# m14sim.net
KiCad netlist of a schematic drawn in Altium Designer
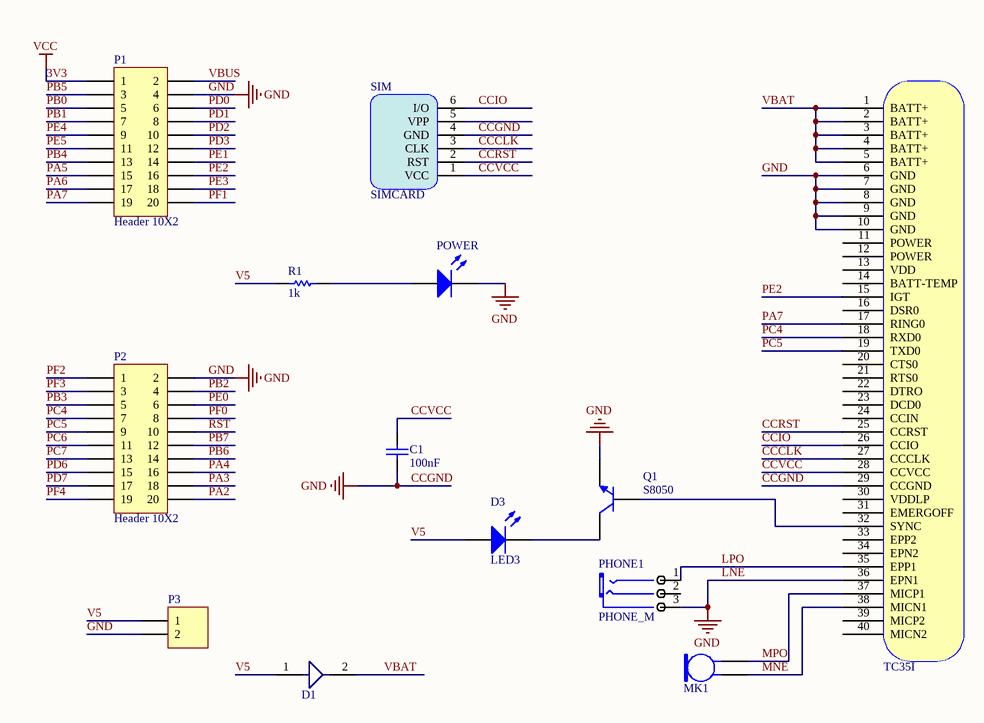
[diagram p0: m14sim.SchDoc]

(export (version "E")
  (design (tool "Eeschema 10.0.6"))
  (components
    (comp (ref "C1")
      (value "100nF")
      (footprint "CAP_0805")
      (description "Capacitor (Semiconductor SIM Model)")
      (fields (field (name "Comment") "Cap Semi") (field (name "PUBLISHER") "Altium Limited"))
      (libsource (lib "Miscellaneous Devices") (part "Cap Semi"))
    )
    (comp (ref "D1") (value "DIAO") (footprint "DIAO") (libsource (lib "LMP3") (part "DIAO")))
    (comp (ref "D3")
      (value "LED3")
      (footprint "LED_0603_RED")
      (description "Typical RED GaAs LED")
      (fields (field (name "PUBLISHER") "Altium Limited"))
      (libsource (lib "Miscellaneous Devices") (part "LED1"))
    )
    (comp (ref "MK1")
      (value "Mic2")
      (footprint "PIN2")
      (description "Microphone")
      (fields (field (name "PUBLISHER") "Altium Limited"))
      (libsource (lib "Miscellaneous Devices") (part "Mic2"))
    )
    (comp (ref "P1")
      (value "Header 10X2")
      (footprint "HDR2X10")
      (description "Header, 10-Pin, Dual row")
      (fields (field (name "PUBLISHER") "Altium Limited"))
      (libsource (lib "Miscellaneous Connectors") (part "Header 10X2"))
    )
    (comp (ref "P2")
      (value "Header 10X2")
      (footprint "HDR2X10")
      (description "Header, 10-Pin, Dual row")
      (fields (field (name "PUBLISHER") "Altium Limited"))
      (libsource (lib "Miscellaneous Connectors") (part "Header 10X2"))
    )
    (comp (ref "P3")
      (value "Header 2")
      (footprint "MKDSN_2RMI")
      (description "Header, 2-Pin")
      (fields (field (name "PUBLISHER") "Altium Limited"))
      (libsource (lib "Miscellaneous Connectors") (part "Header 2"))
    )
    (comp (ref "PHONE1")
      (value "PHONE_M")
      (footprint "PHONE_ST")
      (libsource (lib "战舰STM32开发板底板封装库") (part "PHONE_M"))
    )
    (comp (ref "POWER")
      (value "POWER")
      (footprint "LED_0603_RED")
      (description "Typical RED GaAs LED")
      (fields (field (name "PUBLISHER") "Altium Limited"))
      (libsource (lib "Miscellaneous Devices") (part "LED1"))
    )
    (comp (ref "Q1")
      (value "S8050")
      (footprint "SOT23")
      (description "NPN General-purpose Transistor")
      (fields (field (name "PUBLISHER") "Altium Limited"))
      (libsource (lib "Philips Discrete BJT - Low Power") (part "BC848W"))
    )
    (comp (ref "R1")
      (value "1k")
      (footprint "RES_0603")
      (description "Semiconductor Resistor")
      (fields (field (name "Comment") "Res Semi") (field (name "PUBLISHER") "Altium Limited"))
      (libsource (lib "Miscellaneous Devices") (part "Res Semi"))
    )
    (comp (ref "SIM") (value "SIMCARD") (footprint "SIM6") (libsource (lib "GSM") (part "SIMCARD")))
    (comp (ref "ZIF40") (value "TC35I") (footprint "ZIF") (libsource (lib "GSM") (part "TC35I")))
  )
  (nets
    (net (code "1") (name "/CCCLK") (class "Default")
      (node (ref "SIM") (pin "3") (pinfunction "CLK_3") (pintype "passive"))
      (node (ref "ZIF40") (pin "27") (pinfunction "CCCLK_27") (pintype "passive"))
    )
    (net (code "2") (name "/CCIO") (class "Default")
      (node (ref "SIM") (pin "6") (pinfunction "I/O_6") (pintype "passive"))
      (node (ref "ZIF40") (pin "26") (pinfunction "CCIO_26") (pintype "passive"))
    )
    (net (code "3") (name "/CCRST") (class "Default")
      (node (ref "SIM") (pin "2") (pinfunction "RST_2") (pintype "passive"))
      (node (ref "ZIF40") (pin "25") (pinfunction "CCRST_25") (pintype "passive"))
    )
    (net (code "4") (name "/CCVCC") (class "Default")
      (node (ref "C1") (pin "2") (pinfunction "2_2") (pintype "passive"))
      (node (ref "SIM") (pin "1") (pinfunction "VCC_1") (pintype "passive"))
      (node (ref "ZIF40") (pin "28") (pinfunction "CCVCC_28") (pintype "passive"))
    )
    (net (code "5") (name "/LPO") (class "Default")
      (node (ref "PHONE1") (pin "1") (pinfunction "CHL_1") (pintype "passive"))
      (node (ref "ZIF40") (pin "35") (pinfunction "EPP1_35") (pintype "passive"))
    )
    (net (code "6") (name "/MNE") (class "Default")
      (node (ref "MK1") (pin "1") (pinfunction "1_1") (pintype "passive"))
      (node (ref "ZIF40") (pin "38") (pinfunction "MICN1_38") (pintype "passive"))
    )
    (net (code "7") (name "/MPO") (class "Default")
      (node (ref "MK1") (pin "2") (pinfunction "2_2") (pintype "passive"))
      (node (ref "ZIF40") (pin "37") (pinfunction "MICP1_37") (pintype "passive"))
    )
    (net (code "8") (name "/PA2") (class "Default")
      (node (ref "P2") (pin "20") (pinfunction "20_20") (pintype "passive"))
    )
    (net (code "9") (name "/PA3") (class "Default")
      (node (ref "P2") (pin "18") (pinfunction "18_18") (pintype "passive"))
    )
    (net (code "10") (name "/PA4") (class "Default")
      (node (ref "P2") (pin "16") (pinfunction "16_16") (pintype "passive"))
    )
    (net (code "11") (name "/PA5") (class "Default")
      (node (ref "P1") (pin "15") (pinfunction "15_15") (pintype "passive"))
    )
    (net (code "12") (name "/PA6") (class "Default")
      (node (ref "P1") (pin "17") (pinfunction "17_17") (pintype "passive"))
    )
    (net (code "13") (name "/PA7") (class "Default")
      (node (ref "P1") (pin "19") (pinfunction "19_19") (pintype "passive"))
      (node (ref "ZIF40") (pin "17") (pinfunction "RING0_17") (pintype "passive"))
    )
    (net (code "14") (name "/PB0") (class "Default")
      (node (ref "P1") (pin "5") (pinfunction "5_5") (pintype "passive"))
    )
    (net (code "15") (name "/PB1") (class "Default")
      (node (ref "P1") (pin "7") (pinfunction "7_7") (pintype "passive"))
    )
    (net (code "16") (name "/PB2") (class "Default")
      (node (ref "P2") (pin "4") (pinfunction "4_4") (pintype "passive"))
    )
    (net (code "17") (name "/PB3") (class "Default")
      (node (ref "P2") (pin "5") (pinfunction "5_5") (pintype "passive"))
    )
    (net (code "18") (name "/PB4") (class "Default")
      (node (ref "P1") (pin "13") (pinfunction "13_13") (pintype "passive"))
    )
    (net (code "19") (name "/PB5") (class "Default")
      (node (ref "P1") (pin "3") (pinfunction "3_3") (pintype "passive"))
    )
    (net (code "20") (name "/PB6") (class "Default")
      (node (ref "P2") (pin "14") (pinfunction "14_14") (pintype "passive"))
    )
    (net (code "21") (name "/PB7") (class "Default")
      (node (ref "P2") (pin "12") (pinfunction "12_12") (pintype "passive"))
    )
    (net (code "22") (name "/PC4") (class "Default")
      (node (ref "P2") (pin "7") (pinfunction "7_7") (pintype "passive"))
      (node (ref "ZIF40") (pin "18") (pinfunction "RXD0_18") (pintype "passive"))
    )
    (net (code "23") (name "/PC5") (class "Default")
      (node (ref "P2") (pin "9") (pinfunction "9_9") (pintype "passive"))
      (node (ref "ZIF40") (pin "19") (pinfunction "TXD0_19") (pintype "passive"))
    )
    (net (code "24") (name "/PC6") (class "Default")
      (node (ref "P2") (pin "11") (pinfunction "11_11") (pintype "passive"))
    )
    (net (code "25") (name "/PC7") (class "Default")
      (node (ref "P2") (pin "13") (pinfunction "13_13") (pintype "passive"))
    )
    (net (code "26") (name "/PD0") (class "Default")
      (node (ref "P1") (pin "6") (pinfunction "6_6") (pintype "passive"))
    )
    (net (code "27") (name "/PD1") (class "Default")
      (node (ref "P1") (pin "8") (pinfunction "8_8") (pintype "passive"))
    )
    (net (code "28") (name "/PD2") (class "Default")
      (node (ref "P1") (pin "10") (pinfunction "10_10") (pintype "passive"))
    )
    (net (code "29") (name "/PD3") (class "Default")
      (node (ref "P1") (pin "12") (pinfunction "12_12") (pintype "passive"))
    )
    (net (code "30") (name "/PD6") (class "Default")
      (node (ref "P2") (pin "15") (pinfunction "15_15") (pintype "passive"))
    )
    (net (code "31") (name "/PD7") (class "Default")
      (node (ref "P2") (pin "17") (pinfunction "17_17") (pintype "passive"))
    )
    (net (code "32") (name "/PE0") (class "Default")
      (node (ref "P2") (pin "6") (pinfunction "6_6") (pintype "passive"))
    )
    (net (code "33") (name "/PE1") (class "Default")
      (node (ref "P1") (pin "14") (pinfunction "14_14") (pintype "passive"))
    )
    (net (code "34") (name "/PE2") (class "Default")
      (node (ref "P1") (pin "16") (pinfunction "16_16") (pintype "passive"))
      (node (ref "ZIF40") (pin "15") (pinfunction "IGT_15") (pintype "passive"))
    )
    (net (code "35") (name "/PE3") (class "Default")
      (node (ref "P1") (pin "18") (pinfunction "18_18") (pintype "passive"))
    )
    (net (code "36") (name "/PE4") (class "Default")
      (node (ref "P1") (pin "9") (pinfunction "9_9") (pintype "passive"))
    )
    (net (code "37") (name "/PE5") (class "Default")
      (node (ref "P1") (pin "11") (pinfunction "11_11") (pintype "passive"))
    )
    (net (code "38") (name "/PF0") (class "Default")
      (node (ref "P2") (pin "8") (pinfunction "8_8") (pintype "passive"))
    )
    (net (code "39") (name "/PF1") (class "Default")
      (node (ref "P1") (pin "20") (pinfunction "20_20") (pintype "passive"))
    )
    (net (code "40") (name "/PF2") (class "Default")
      (node (ref "P2") (pin "1") (pinfunction "1_1") (pintype "passive"))
    )
    (net (code "41") (name "/PF3") (class "Default")
      (node (ref "P2") (pin "3") (pinfunction "3_3") (pintype "passive"))
    )
    (net (code "42") (name "/PF4") (class "Default")
      (node (ref "P2") (pin "19") (pinfunction "19_19") (pintype "passive"))
    )
    (net (code "43") (name "/RST") (class "Default")
      (node (ref "P2") (pin "10") (pinfunction "10_10") (pintype "passive"))
    )
    (net (code "44") (name "/V5") (class "Default")
      (node (ref "D1") (pin "1") (pinfunction "1_1") (pintype "passive"))
      (node (ref "D3") (pin "1") (pinfunction "A_1") (pintype "passive"))
      (node (ref "P3") (pin "1") (pinfunction "1_1") (pintype "passive"))
      (node (ref "R1") (pin "2") (pinfunction "2_2") (pintype "passive"))
    )
    (net (code "45") (name "/VBAT") (class "Default")
      (node (ref "D1") (pin "2") (pinfunction "2_2") (pintype "passive"))
      (node (ref "ZIF40") (pin "1") (pinfunction "BATT+_1") (pintype "passive"))
      (node (ref "ZIF40") (pin "2") (pinfunction "BATT+_2") (pintype "passive"))
      (node (ref "ZIF40") (pin "3") (pinfunction "BATT+_3") (pintype "passive"))
      (node (ref "ZIF40") (pin "4") (pinfunction "BATT+_4") (pintype "passive"))
      (node (ref "ZIF40") (pin "5") (pinfunction "BATT+_5") (pintype "passive"))
    )
    (net (code "46") (name "/VBUS") (class "Default")
      (node (ref "P1") (pin "2") (pinfunction "2_2") (pintype "passive"))
    )
    (net (code "47") (name "GND") (class "Default")
      (node (ref "C1") (pin "1") (pinfunction "1_1") (pintype "passive"))
      (node (ref "P1") (pin "4") (pinfunction "4_4") (pintype "passive"))
      (node (ref "P2") (pin "2") (pinfunction "2_2") (pintype "passive"))
      (node (ref "P3") (pin "2") (pinfunction "2_2") (pintype "passive"))
      (node (ref "PHONE1") (pin "3") (pinfunction "COM_3") (pintype "passive"))
      (node (ref "POWER") (pin "2") (pinfunction "K_2") (pintype "passive"))
      (node (ref "Q1") (pin "2") (pinfunction "E_2") (pintype "passive"))
      (node (ref "SIM") (pin "4") (pinfunction "GND_4") (pintype "passive"))
      (node (ref "ZIF40") (pin "10") (pinfunction "GND_10") (pintype "passive"))
      (node (ref "ZIF40") (pin "29") (pinfunction "CCGND_29") (pintype "passive"))
      (node (ref "ZIF40") (pin "36") (pinfunction "EPN1_36") (pintype "passive"))
      (node (ref "ZIF40") (pin "6") (pinfunction "GND_6") (pintype "passive"))
      (node (ref "ZIF40") (pin "7") (pinfunction "GND_7") (pintype "passive"))
      (node (ref "ZIF40") (pin "8") (pinfunction "GND_8") (pintype "passive"))
      (node (ref "ZIF40") (pin "9") (pinfunction "GND_9") (pintype "passive"))
    )
    (net (code "48") (name "Net-(D3-K)") (class "Default")
      (node (ref "D3") (pin "2") (pinfunction "K_2") (pintype "passive"))
      (node (ref "Q1") (pin "3") (pinfunction "C_3") (pintype "passive"))
    )
    (net (code "49") (name "Net-(POWER-A)") (class "Default")
      (node (ref "POWER") (pin "1") (pinfunction "A_1") (pintype "passive"))
      (node (ref "R1") (pin "1") (pinfunction "1_1") (pintype "passive"))
    )
    (net (code "50") (name "Net-(Q1-B)") (class "Default")
      (node (ref "Q1") (pin "1") (pinfunction "B_1") (pintype "passive"))
      (node (ref "ZIF40") (pin "32") (pinfunction "SYNC_32") (pintype "passive"))
    )
    (net (code "51") (name "VCC") (class "Default")
      (node (ref "P1") (pin "1") (pinfunction "1_1") (pintype "passive"))
    )
    (net (code "52") (name "unconnected-(PHONE1-CHR-Pad2)") (class "Default")
      (node (ref "PHONE1") (pin "2") (pinfunction "CHR_2") (pintype "passive"))
    )
    (net (code "53") (name "unconnected-(SIM-VPP-Pad5)") (class "Default")
      (node (ref "SIM") (pin "5") (pinfunction "VPP_5") (pintype "passive"))
    )
    (net (code "54") (name "unconnected-(ZIF40-BATT-TEMP-Pad14)") (class "Default")
      (node (ref "ZIF40") (pin "14") (pinfunction "BATT-TEMP_14") (pintype "passive"))
    )
    (net (code "55") (name "unconnected-(ZIF40-CCIN-Pad24)") (class "Default")
      (node (ref "ZIF40") (pin "24") (pinfunction "CCIN_24") (pintype "passive"))
    )
    (net (code "56") (name "unconnected-(ZIF40-CTS0-Pad20)") (class "Default")
      (node (ref "ZIF40") (pin "20") (pinfunction "CTS0_20") (pintype "passive"))
    )
    (net (code "57") (name "unconnected-(ZIF40-DCD0-Pad23)") (class "Default")
      (node (ref "ZIF40") (pin "23") (pinfunction "DCD0_23") (pintype "passive"))
    )
    (net (code "58") (name "unconnected-(ZIF40-DSR0-Pad16)") (class "Default")
      (node (ref "ZIF40") (pin "16") (pinfunction "DSR0_16") (pintype "passive"))
    )
    (net (code "59") (name "unconnected-(ZIF40-DTRO-Pad22)") (class "Default")
      (node (ref "ZIF40") (pin "22") (pinfunction "DTRO_22") (pintype "passive"))
    )
    (net (code "60") (name "unconnected-(ZIF40-EMERGOFF-Pad31)") (class "Default")
      (node (ref "ZIF40") (pin "31") (pinfunction "EMERGOFF_31") (pintype "passive"))
    )
    (net (code "61") (name "unconnected-(ZIF40-EPN2-Pad34)") (class "Default")
      (node (ref "ZIF40") (pin "34") (pinfunction "EPN2_34") (pintype "passive"))
    )
    (net (code "62") (name "unconnected-(ZIF40-EPP2-Pad33)") (class "Default")
      (node (ref "ZIF40") (pin "33") (pinfunction "EPP2_33") (pintype "passive"))
    )
    (net (code "63") (name "unconnected-(ZIF40-MICN2-Pad40)") (class "Default")
      (node (ref "ZIF40") (pin "40") (pinfunction "MICN2_40") (pintype "passive"))
    )
    (net (code "64") (name "unconnected-(ZIF40-MICP2-Pad39)") (class "Default")
      (node (ref "ZIF40") (pin "39") (pinfunction "MICP2_39") (pintype "passive"))
    )
    (net (code "65") (name "unconnected-(ZIF40-POWER-Pad11)") (class "Default")
      (node (ref "ZIF40") (pin "11") (pinfunction "POWER_11") (pintype "passive"))
    )
    (net (code "66") (name "unconnected-(ZIF40-POWER-Pad12)") (class "Default")
      (node (ref "ZIF40") (pin "12") (pinfunction "POWER_12") (pintype "passive"))
    )
    (net (code "67") (name "unconnected-(ZIF40-RTS0-Pad21)") (class "Default")
      (node (ref "ZIF40") (pin "21") (pinfunction "RTS0_21") (pintype "passive"))
    )
    (net (code "68") (name "unconnected-(ZIF40-VDD-Pad13)") (class "Default")
      (node (ref "ZIF40") (pin "13") (pinfunction "VDD_13") (pintype "passive"))
    )
    (net (code "69") (name "unconnected-(ZIF40-VDDLP-Pad30)") (class "Default")
      (node (ref "ZIF40") (pin "30") (pinfunction "VDDLP_30") (pintype "passive"))
    )
  )
)
